# APDS9960.net
KiCad netlist of a schematic drawn in Altium Designer
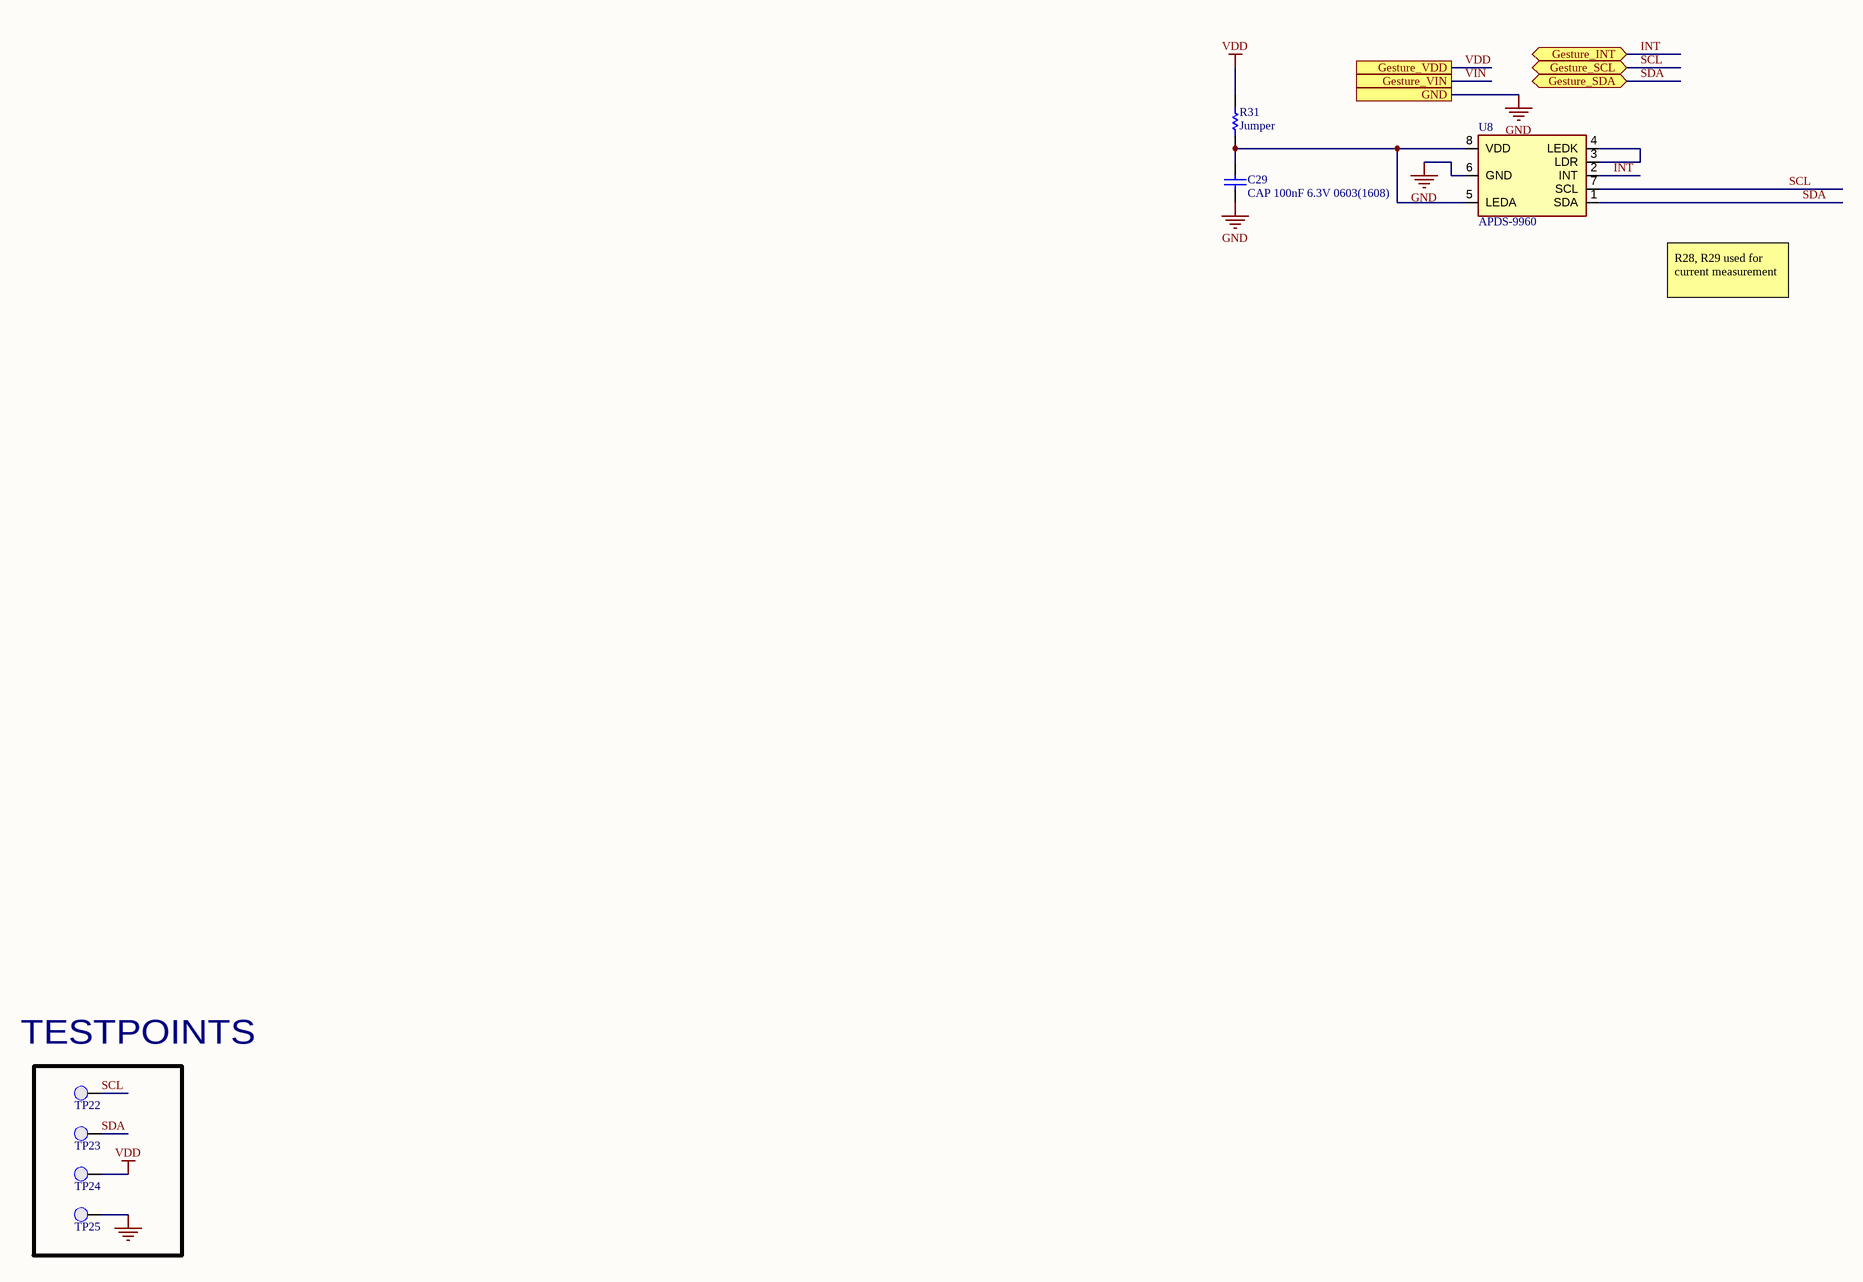
[diagram p0: APDS9960.SchDoc]

(export (version "E")
  (design (tool "Eeschema 10.0.6"))
  (components
    (comp (ref "C29")
      (value "CAP 100nF 6.3V 0603(1608)")
      (footprint "CAPC0603(1608)100_M")
      (description "CAP 100nF 6.3V ±5% 0603 (1608 Metric) Thickness 1mm SMD")
      (fields (field (name "TOLERANCE") "Â±5%"))
      (libsource (lib "Altium Content Vault") (part "CAP"))
    )
    (comp (ref "R31")
      (value "Jumper")
      (footprint "RESC0603(1608)_N")
      (description "Jumper 0603 (1608 Metric)")
      (fields (field (name "POWER") "None"))
      (libsource (lib "Altium Content Vault") (part "RES"))
    )
    (comp (ref "TP22")
      (value "0.1\" Pad")
      (footprint "PCBComponent")
      (libsource (lib "Components - 12.02.20 - 18.05") (part "0.1{dblquote} Pad-A.4"))
    )
    (comp (ref "TP23")
      (value "0.1\" Pad")
      (footprint "PCBComponent")
      (libsource (lib "Components - 12.02.20 - 18.05") (part "0.1{dblquote} Pad-A.4"))
    )
    (comp (ref "TP24")
      (value "0.1\" Pad")
      (footprint "PCBComponent")
      (libsource (lib "Components - 12.02.20 - 18.05") (part "0.1{dblquote} Pad-A.4"))
    )
    (comp (ref "TP25")
      (value "0.1\" Pad")
      (footprint "PCBComponent")
      (libsource (lib "Components - 12.02.20 - 18.05") (part "0.1{dblquote} Pad-A.4"))
    )
    (comp (ref "U8")
      (value "APDS-9960")
      (footprint "APDS-9960")
      (fields (field (name "MF") "{'manufacturer': u'Broadcom Limited'}"))
      (libsource (lib "SnapEDA_Library") (part "APDS-9960"))
    )
  )
  (nets
    (net (code "1") (name "/INT") (class "Default")
      (node (ref "U8") (pin "2") (pinfunction "INT_2") (pintype "bidirectional"))
    )
    (net (code "2") (name "/SCL") (class "Default")
      (node (ref "TP22") (pin "1") (pinfunction "PAD_1") (pintype "passive"))
      (node (ref "U8") (pin "7") (pinfunction "SCL_7") (pintype "bidirectional"))
    )
    (net (code "3") (name "/SDA") (class "Default")
      (node (ref "TP23") (pin "1") (pinfunction "PAD_1") (pintype "passive"))
      (node (ref "U8") (pin "1") (pinfunction "SDA_1") (pintype "bidirectional"))
    )
    (net (code "5") (name "GND") (class "Default")
      (node (ref "C29") (pin "2") (pinfunction "2_2") (pintype "passive"))
      (node (ref "TP25") (pin "1") (pinfunction "PAD_1") (pintype "passive"))
      (node (ref "U8") (pin "6") (pinfunction "GND_6") (pintype "bidirectional"))
    )
    (net (code "6") (name "Net-(U8-LDR)") (class "Default")
      (node (ref "U8") (pin "3") (pinfunction "LDR_3") (pintype "bidirectional"))
      (node (ref "U8") (pin "4") (pinfunction "LEDK_4") (pintype "bidirectional"))
    )
    (net (code "7") (name "Net-(U8-LEDA)") (class "Default")
      (node (ref "C29") (pin "1") (pinfunction "1_1") (pintype "passive"))
      (node (ref "R31") (pin "2") (pinfunction "2_2") (pintype "passive"))
      (node (ref "U8") (pin "5") (pinfunction "LEDA_5") (pintype "bidirectional"))
      (node (ref "U8") (pin "8") (pinfunction "VDD_8") (pintype "bidirectional"))
    )
    (net (code "8") (name "VDD") (class "Default")
      (node (ref "R31") (pin "1") (pinfunction "1_1") (pintype "passive"))
      (node (ref "TP24") (pin "1") (pinfunction "PAD_1") (pintype "passive"))
    )
  )
)
